# USB_Power__V1.net
KiCad netlist of a schematic drawn in EAGLE
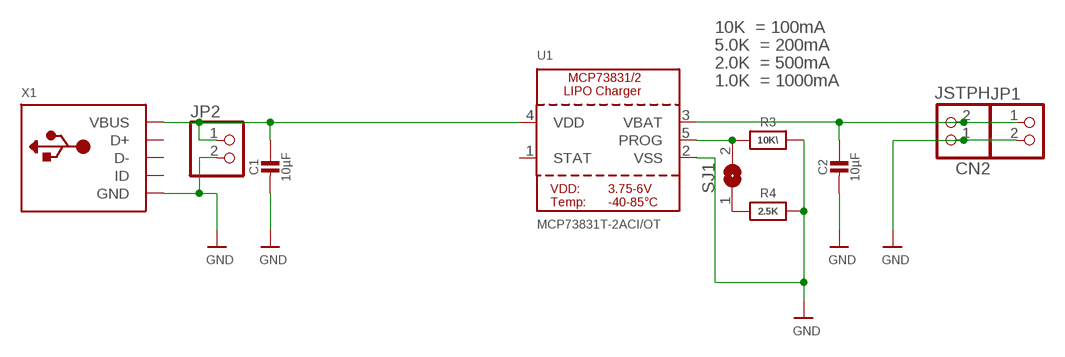
[diagram p0: schematic, sheet 1]

(export (version "E")
  (design (tool "Eeschema 10.0.6"))
  (components
    (comp (ref "C1")
      (value "10µF")
      (footprint "eagle-import:0805-NO")
      (libsource (lib "eagle-import") (part "CAP_CERAMIC0805-NOOUTLINE"))
    )
    (comp (ref "C2")
      (value "10µF")
      (footprint "eagle-import:0805-NO")
      (libsource (lib "eagle-import") (part "CAP_CERAMIC0805-NOOUTLINE"))
    )
    (comp (ref "CN2")
      (value "JSTPH")
      (footprint "eagle-import:JSTPH2")
      (libsource (lib "eagle-import") (part "JST_2PIN"))
    )
    (comp (ref "JP1")
      (value "HEADER-1X2ROUND")
      (footprint "eagle-import:1X02_ROUND")
      (libsource (lib "eagle-import") (part "HEADER-1X2ROUND"))
    )
    (comp (ref "JP2")
      (value "HEADER-1X2ROUND")
      (footprint "eagle-import:1X02_ROUND")
      (libsource (lib "eagle-import") (part "HEADER-1X2ROUND"))
    )
    (comp (ref "R3")
      (value "10K\\")
      (footprint "eagle-import:0805-NO")
      (libsource (lib "eagle-import") (part "RESISTOR0805_NOOUTLINE"))
    )
    (comp (ref "R4")
      (value "2.5K")
      (footprint "eagle-import:0805-NO")
      (libsource (lib "eagle-import") (part "RESISTOR0805_NOOUTLINE"))
    )
    (comp (ref "SJ1")
      (value "SOLDERJUMPER")
      (footprint "eagle-import:SOLDERJUMPER_ARROW_NOPASTE")
      (libsource (lib "eagle-import") (part "SOLDERJUMPER"))
    )
    (comp (ref "U1")
      (value "MCP73831T-2ACI/OT")
      (footprint "eagle-import:SOT23-5")
      (libsource (lib "eagle-import") (part "MCP73831/2"))
    )
    (comp (ref "X1")
      (value "USB_MEDIUM")
      (footprint "eagle-import:USB-MINI_MEDIUM")
      (libsource (lib "eagle-import") (part "USB_MEDIUM"))
    )
  )
  (nets
    (net (code "1") (name "GND") (class "Default")
      (node (ref "C1") (pin "2") (pinfunction "2_2") (pintype "passive"))
      (node (ref "C2") (pin "2") (pinfunction "2_2") (pintype "passive"))
      (node (ref "CN2") (pin "1") (pinfunction "1_1") (pintype "passive"))
      (node (ref "JP1") (pin "2") (pinfunction "2_2") (pintype "passive"))
      (node (ref "JP2") (pin "2") (pinfunction "2_2") (pintype "passive"))
      (node (ref "R3") (pin "2") (pinfunction "2_2") (pintype "passive"))
      (node (ref "R4") (pin "2") (pinfunction "2_2") (pintype "passive"))
      (node (ref "U1") (pin "2") (pinfunction "VSS_2") (pintype "power_in"))
      (node (ref "X1") (pin "GND") (pinfunction "GND_GND") (pintype "power_in"))
      (node (ref "X1") (pin "GND1") (pinfunction "GND_GND1") (pintype "power_in"))
      (node (ref "X1") (pin "GND2") (pinfunction "GND_GND2") (pintype "power_in"))
      (node (ref "X1") (pin "GND3") (pinfunction "GND_GND3") (pintype "power_in"))
      (node (ref "X1") (pin "GND4") (pinfunction "GND_GND4") (pintype "power_in"))
    )
    (net (code "2") (name "Net-(R4-Pad1)") (class "Default")
      (node (ref "R4") (pin "1") (pinfunction "1_1") (pintype "passive"))
      (node (ref "SJ1") (pin "1") (pinfunction "1_1") (pintype "passive"))
    )
    (net (code "3") (name "Net-(U1-PROG)") (class "Default")
      (node (ref "R3") (pin "1") (pinfunction "1_1") (pintype "passive"))
      (node (ref "SJ1") (pin "2") (pinfunction "2_2") (pintype "passive"))
      (node (ref "U1") (pin "5") (pinfunction "PROG_5") (pintype "input"))
    )
    (net (code "4") (name "Net-(U1-VBAT)") (class "Default")
      (node (ref "C2") (pin "1") (pinfunction "1_1") (pintype "passive"))
      (node (ref "CN2") (pin "2") (pinfunction "2_2") (pintype "passive"))
      (node (ref "JP1") (pin "1") (pinfunction "1_1") (pintype "passive"))
      (node (ref "U1") (pin "3") (pinfunction "VBAT_3") (pintype "power_in"))
    )
    (net (code "5") (name "Net-(U1-VDD)") (class "Default")
      (node (ref "C1") (pin "1") (pinfunction "1_1") (pintype "passive"))
      (node (ref "JP2") (pin "1") (pinfunction "1_1") (pintype "passive"))
      (node (ref "U1") (pin "4") (pinfunction "VDD_4") (pintype "power_in"))
      (node (ref "X1") (pin "VBUS") (pinfunction "VBUS_VBUS") (pintype "power_in"))
    )
    (net (code "6") (name "unconnected-(U1-STAT-Pad1)") (class "Default")
      (node (ref "U1") (pin "1") (pinfunction "STAT_1") (pintype "output"))
    )
    (net (code "7") (name "unconnected-(X1-PadD+)") (class "Default")
      (node (ref "X1") (pin "D+") (pinfunction "D+_D+") (pintype "bidirectional"))
    )
    (net (code "8") (name "unconnected-(X1-PadD-)") (class "Default")
      (node (ref "X1") (pin "D-") (pinfunction "D-_D-") (pintype "bidirectional"))
    )
    (net (code "9") (name "unconnected-(X1-PadID)") (class "Default")
      (node (ref "X1") (pin "ID") (pinfunction "ID_ID") (pintype "bidirectional"))
    )
  )
)
